# max6120.net
KiCad netlist of a schematic drawn in EAGLE
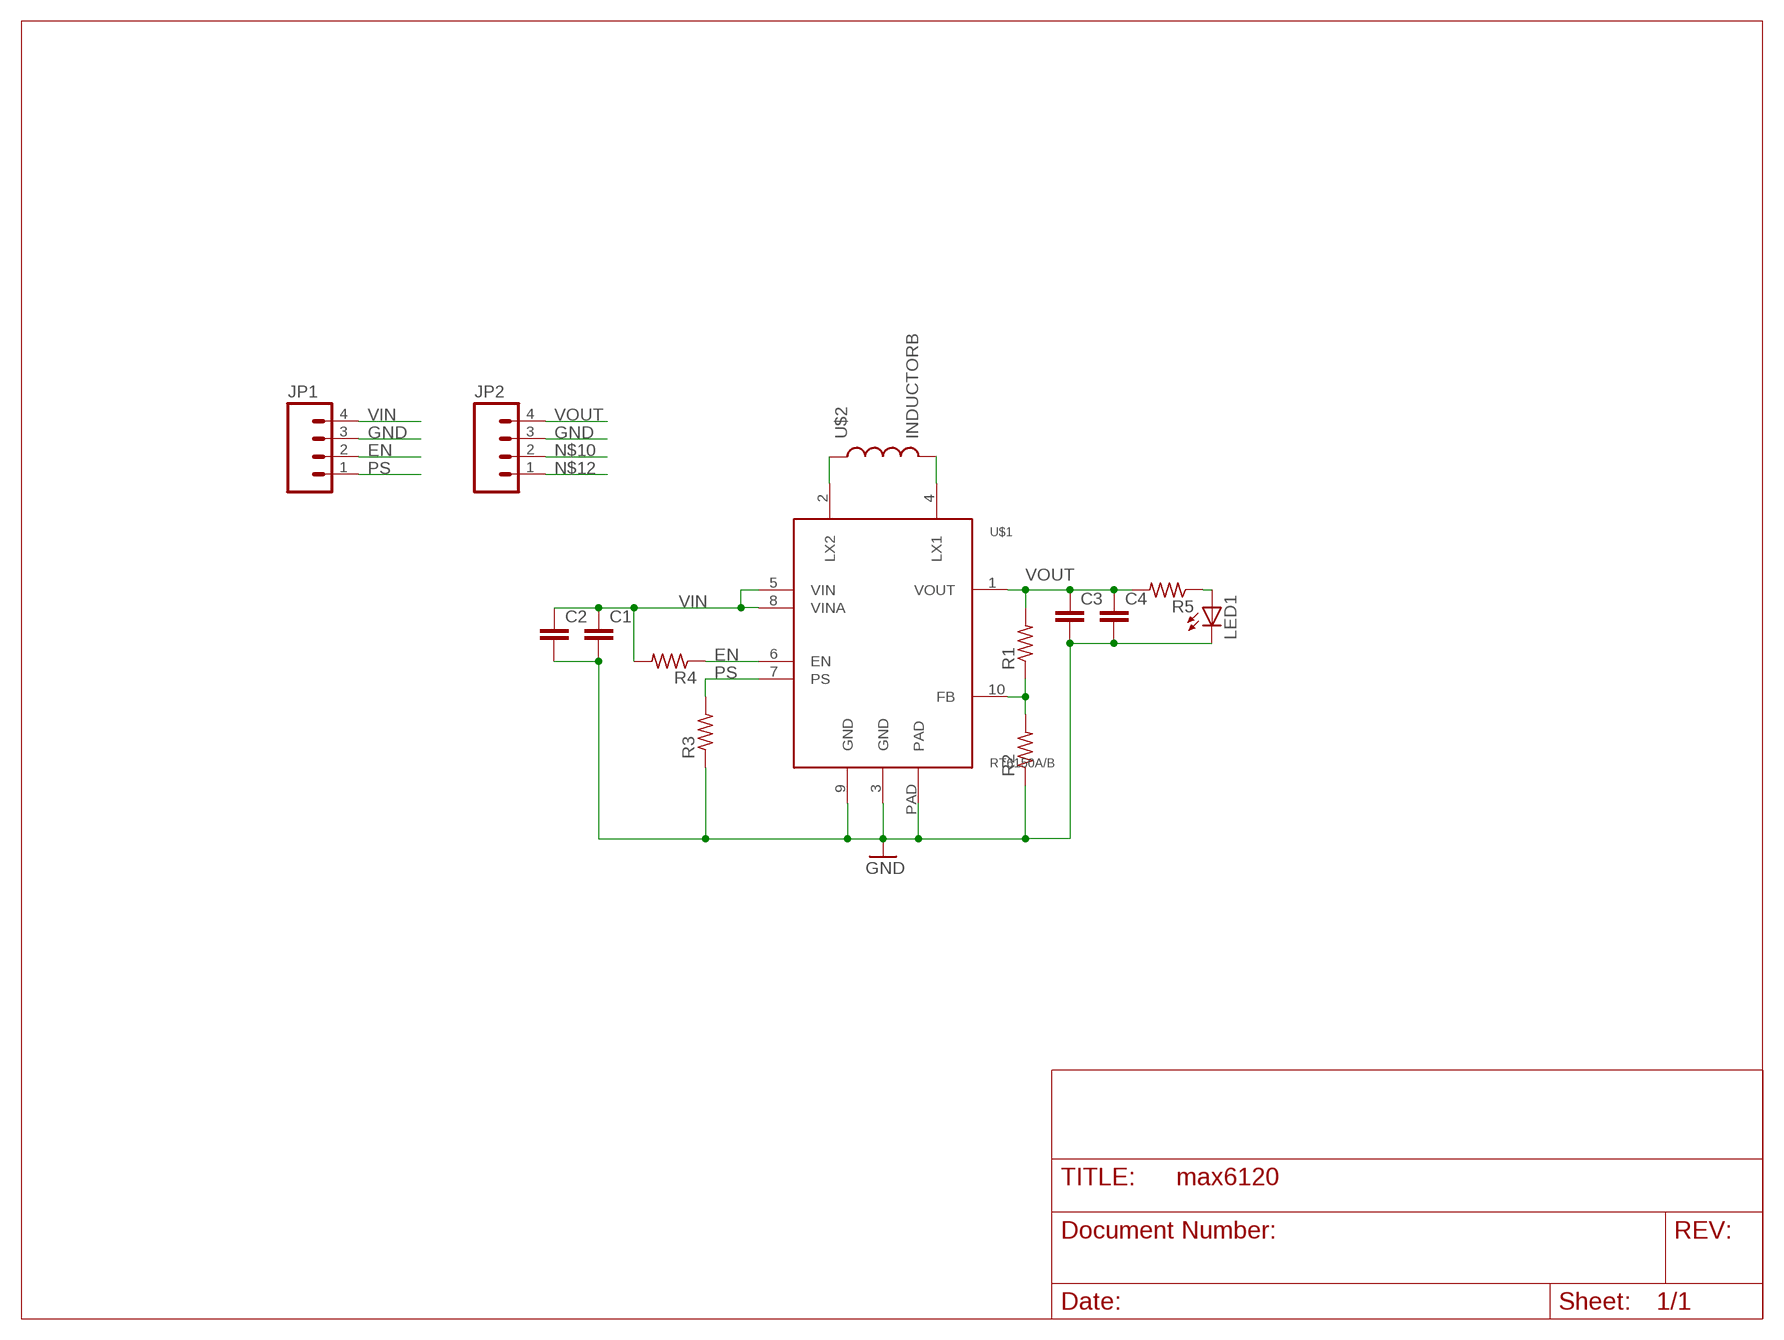
[diagram p0: schematic, sheet 1]

(export (version "E")
  (design (tool "Eeschema 10.0.6"))
  (components
    (comp (ref "C1")
      (value "C-EUC0603")
      (footprint "eagle-import:C0603")
      (libsource (lib "eagle-import") (part "C-EUC0603"))
    )
    (comp (ref "C2")
      (value "C-EUC0603")
      (footprint "eagle-import:C0603")
      (libsource (lib "eagle-import") (part "C-EUC0603"))
    )
    (comp (ref "C3")
      (value "C-EUC0603")
      (footprint "eagle-import:C0603")
      (libsource (lib "eagle-import") (part "C-EUC0603"))
    )
    (comp (ref "C4")
      (value "C-EUC0603")
      (footprint "eagle-import:C0603")
      (libsource (lib "eagle-import") (part "C-EUC0603"))
    )
    (comp (ref "JP1")
      (value "M041X04_NO_SILK")
      (footprint "eagle-import:1X04_NO_SILK")
      (libsource (lib "eagle-import") (part "M041X04_NO_SILK"))
    )
    (comp (ref "JP2")
      (value "M041X04_NO_SILK")
      (footprint "eagle-import:1X04_NO_SILK")
      (libsource (lib "eagle-import") (part "M041X04_NO_SILK"))
    )
    (comp (ref "LED1")
      (value "LEDCHIP-LED0603")
      (footprint "eagle-import:CHIP-LED0603")
      (libsource (lib "eagle-import") (part "LEDCHIP-LED0603"))
    )
    (comp (ref "R1")
      (value "R-US_R0402")
      (footprint "eagle-import:R0402")
      (libsource (lib "eagle-import") (part "R-US_R0402"))
    )
    (comp (ref "R2")
      (value "R-US_R0402")
      (footprint "eagle-import:R0402")
      (libsource (lib "eagle-import") (part "R-US_R0402"))
    )
    (comp (ref "R3")
      (value "R-US_R0402")
      (footprint "eagle-import:R0402")
      (libsource (lib "eagle-import") (part "R-US_R0402"))
    )
    (comp (ref "R4")
      (value "R-US_R0402")
      (footprint "eagle-import:R0402")
      (libsource (lib "eagle-import") (part "R-US_R0402"))
    )
    (comp (ref "R5")
      (value "R-US_R0402")
      (footprint "eagle-import:R0402")
      (libsource (lib "eagle-import") (part "R-US_R0402"))
    )
    (comp (ref "U$1")
      (value "RT6150A/B")
      (footprint "eagle-import:DFN3X310L")
      (libsource (lib "eagle-import") (part "RT6150A/B"))
    )
    (comp (ref "U$2")
      (value "INDUCTORB")
      (footprint "eagle-import:INDUCTOR-NR3015")
      (libsource (lib "eagle-import") (part "INDUCTORB"))
    )
  )
  (nets
    (net (code "1") (name "/EN") (class "Default")
      (node (ref "JP1") (pin "2") (pinfunction "2_2") (pintype "passive"))
      (node (ref "R4") (pin "1") (pinfunction "1_1") (pintype "passive"))
      (node (ref "U$1") (pin "6") (pinfunction "EN_6") (pintype "bidirectional"))
    )
    (net (code "2") (name "/N$10") (class "Default")
      (node (ref "JP2") (pin "2") (pinfunction "2_2") (pintype "passive"))
    )
    (net (code "3") (name "/N$12") (class "Default")
      (node (ref "JP2") (pin "1") (pinfunction "1_1") (pintype "passive"))
    )
    (net (code "4") (name "/PS") (class "Default")
      (node (ref "JP1") (pin "1") (pinfunction "1_1") (pintype "passive"))
      (node (ref "R3") (pin "2") (pinfunction "2_2") (pintype "passive"))
      (node (ref "U$1") (pin "7") (pinfunction "PS_7") (pintype "bidirectional"))
    )
    (net (code "5") (name "/VIN") (class "Default")
      (node (ref "C1") (pin "1") (pinfunction "1_1") (pintype "passive"))
      (node (ref "C2") (pin "1") (pinfunction "1_1") (pintype "passive"))
      (node (ref "JP1") (pin "4") (pinfunction "4_4") (pintype "passive"))
      (node (ref "R4") (pin "2") (pinfunction "2_2") (pintype "passive"))
      (node (ref "U$1") (pin "5") (pinfunction "VIN_5") (pintype "bidirectional"))
      (node (ref "U$1") (pin "8") (pinfunction "VINA_8") (pintype "bidirectional"))
    )
    (net (code "6") (name "/VOUT") (class "Default")
      (node (ref "C3") (pin "1") (pinfunction "1_1") (pintype "passive"))
      (node (ref "C4") (pin "1") (pinfunction "1_1") (pintype "passive"))
      (node (ref "JP2") (pin "4") (pinfunction "4_4") (pintype "passive"))
      (node (ref "R1") (pin "2") (pinfunction "2_2") (pintype "passive"))
      (node (ref "R5") (pin "2") (pinfunction "2_2") (pintype "passive"))
      (node (ref "U$1") (pin "1") (pinfunction "VOUT_1") (pintype "bidirectional"))
    )
    (net (code "7") (name "GND") (class "Default")
      (node (ref "C1") (pin "2") (pinfunction "2_2") (pintype "passive"))
      (node (ref "C2") (pin "2") (pinfunction "2_2") (pintype "passive"))
      (node (ref "C3") (pin "2") (pinfunction "2_2") (pintype "passive"))
      (node (ref "C4") (pin "2") (pinfunction "2_2") (pintype "passive"))
      (node (ref "JP1") (pin "3") (pinfunction "3_3") (pintype "passive"))
      (node (ref "JP2") (pin "3") (pinfunction "3_3") (pintype "passive"))
      (node (ref "LED1") (pin "C") (pinfunction "C_C") (pintype "passive"))
      (node (ref "R2") (pin "1") (pinfunction "1_1") (pintype "passive"))
      (node (ref "R3") (pin "1") (pinfunction "1_1") (pintype "passive"))
      (node (ref "U$1") (pin "3") (pinfunction "GND_3") (pintype "bidirectional"))
      (node (ref "U$1") (pin "9") (pinfunction "GND_9") (pintype "bidirectional"))
      (node (ref "U$1") (pin "PAD") (pinfunction "PAD_PAD") (pintype "bidirectional"))
    )
    (net (code "8") (name "Net-(LED1-PadA)") (class "Default")
      (node (ref "LED1") (pin "A") (pinfunction "A_A") (pintype "passive"))
      (node (ref "R5") (pin "1") (pinfunction "1_1") (pintype "passive"))
    )
    (net (code "9") (name "Net-(U$1-FB)") (class "Default")
      (node (ref "R1") (pin "1") (pinfunction "1_1") (pintype "passive"))
      (node (ref "R2") (pin "2") (pinfunction "2_2") (pintype "passive"))
      (node (ref "U$1") (pin "10") (pinfunction "FB_10") (pintype "bidirectional"))
    )
    (net (code "10") (name "Net-(U$1-LX1)") (class "Default")
      (node (ref "U$1") (pin "4") (pinfunction "LX1_4") (pintype "bidirectional"))
      (node (ref "U$2") (pin "2") (pinfunction "2_2") (pintype "passive"))
    )
    (net (code "11") (name "Net-(U$1-LX2)") (class "Default")
      (node (ref "U$1") (pin "2") (pinfunction "LX2_2") (pintype "bidirectional"))
      (node (ref "U$2") (pin "1") (pinfunction "1_1") (pintype "passive"))
    )
  )
)
